# teste2.net
KiCad netlist of a schematic drawn in EAGLE
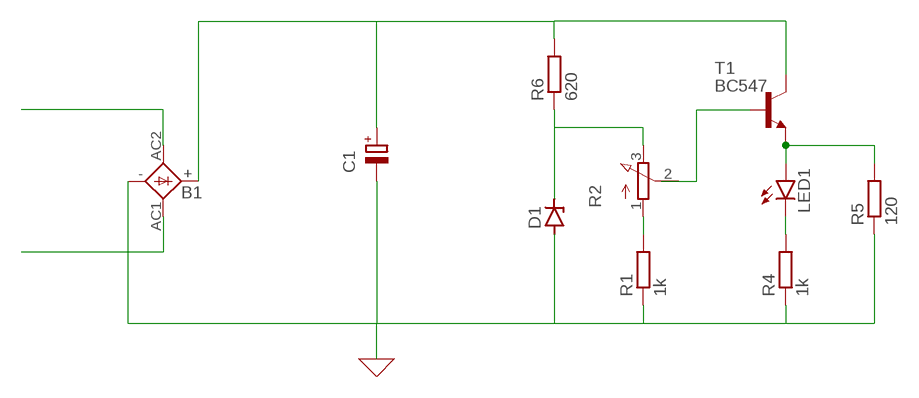
[diagram p0: schematic, sheet 1]

(export (version "E")
  (design (tool "Eeschema 10.0.6"))
  (components
    (comp (ref "B1")
      (value "KBL")
      (footprint "eagle-import:KBL")
      (libsource (lib "eagle-import") (part "KBL"))
    )
    (comp (ref "C1")
      (value "CPOL-EUE5-10.5")
      (footprint "eagle-import:E5-10,5")
      (libsource (lib "eagle-import") (part "CPOL-EUE5-10.5"))
    )
    (comp (ref "D1")
      (value "ZENER-DIODEDO41Z10")
      (footprint "eagle-import:DO41Z10")
      (libsource (lib "eagle-import") (part "ZENER-DIODEDO41Z10"))
    )
    (comp (ref "LED1")
      (value "LED5MM")
      (footprint "eagle-import:LED5MM")
      (libsource (lib "eagle-import") (part "LED5MM"))
    )
    (comp (ref "R1")
      (value "1k")
      (footprint "eagle-import:0204V")
      (libsource (lib "eagle-import") (part "R-EU_0204/2V"))
    )
    (comp (ref "R2")
      (value "3RP/1610N")
      (footprint "eagle-import:3RP_1610N")
      (libsource (lib "eagle-import") (part "3RP/1610N"))
    )
    (comp (ref "R4")
      (value "1k")
      (footprint "eagle-import:0204V")
      (libsource (lib "eagle-import") (part "R-EU_0204/2V"))
    )
    (comp (ref "R5")
      (value "120")
      (footprint "eagle-import:0204V")
      (libsource (lib "eagle-import") (part "R-EU_0204/2V"))
    )
    (comp (ref "R6")
      (value "620")
      (footprint "eagle-import:0204V")
      (libsource (lib "eagle-import") (part "R-EU_0204/2V"))
    )
    (comp (ref "T1")
      (value "BC547")
      (footprint "eagle-import:TO92")
      (libsource (lib "eagle-import") (part "BC547"))
    )
  )
  (nets
    (net (code "1") (name "GND") (class "Default")
      (node (ref "B1") (pin "-") (pinfunction "-_-") (pintype "passive"))
      (node (ref "C1") (pin "-") (pinfunction "-_-") (pintype "passive"))
      (node (ref "D1") (pin "A") (pinfunction "A_A") (pintype "passive"))
      (node (ref "R1") (pin "1") (pinfunction "1_1") (pintype "passive"))
      (node (ref "R4") (pin "1") (pinfunction "1_1") (pintype "passive"))
      (node (ref "R5") (pin "1") (pinfunction "1_1") (pintype "passive"))
    )
    (net (code "2") (name "Net-(LED1-C)") (class "Default")
      (node (ref "LED1") (pin "K") (pinfunction "C_K") (pintype "passive"))
      (node (ref "R4") (pin "2") (pinfunction "2_2") (pintype "passive"))
    )
    (net (code "3") (name "Net-(R2-A)") (class "Default")
      (node (ref "R1") (pin "2") (pinfunction "2_2") (pintype "passive"))
      (node (ref "R2") (pin "1") (pinfunction "A_1") (pintype "passive"))
    )
    (net (code "4") (name "Net-(R2-E)") (class "Default")
      (node (ref "D1") (pin "C") (pinfunction "C_C") (pintype "passive"))
      (node (ref "R2") (pin "3") (pinfunction "E_3") (pintype "passive"))
      (node (ref "R6") (pin "1") (pinfunction "1_1") (pintype "passive"))
    )
    (net (code "5") (name "Net-(R2-S)") (class "Default")
      (node (ref "R2") (pin "2") (pinfunction "S_2") (pintype "passive"))
      (node (ref "T1") (pin "2") (pinfunction "B_2") (pintype "passive"))
    )
    (net (code "6") (name "Net-(T1-C)") (class "Default")
      (node (ref "B1") (pin "+") (pinfunction "+_+") (pintype "passive"))
      (node (ref "C1") (pin "+") (pinfunction "+_+") (pintype "passive"))
      (node (ref "R6") (pin "2") (pinfunction "2_2") (pintype "passive"))
      (node (ref "T1") (pin "3") (pinfunction "C_3") (pintype "passive"))
    )
    (net (code "7") (name "Net-(T1-E)") (class "Default")
      (node (ref "LED1") (pin "A") (pinfunction "A_A") (pintype "passive"))
      (node (ref "R5") (pin "2") (pinfunction "2_2") (pintype "passive"))
      (node (ref "T1") (pin "1") (pinfunction "E_1") (pintype "passive"))
    )
    (net (code "8") (name "unconnected-(B1-AC1-PadAC2)") (class "Default")
      (node (ref "B1") (pin "AC2") (pinfunction "AC1_AC2") (pintype "passive"))
    )
    (net (code "9") (name "unconnected-(B1-AC2-PadAC1)") (class "Default")
      (node (ref "B1") (pin "AC1") (pinfunction "AC2_AC1") (pintype "passive"))
    )
  )
)
